# RHD2132_lvds_headstage_50mil.net
KiCad netlist of a schematic drawn in EAGLE
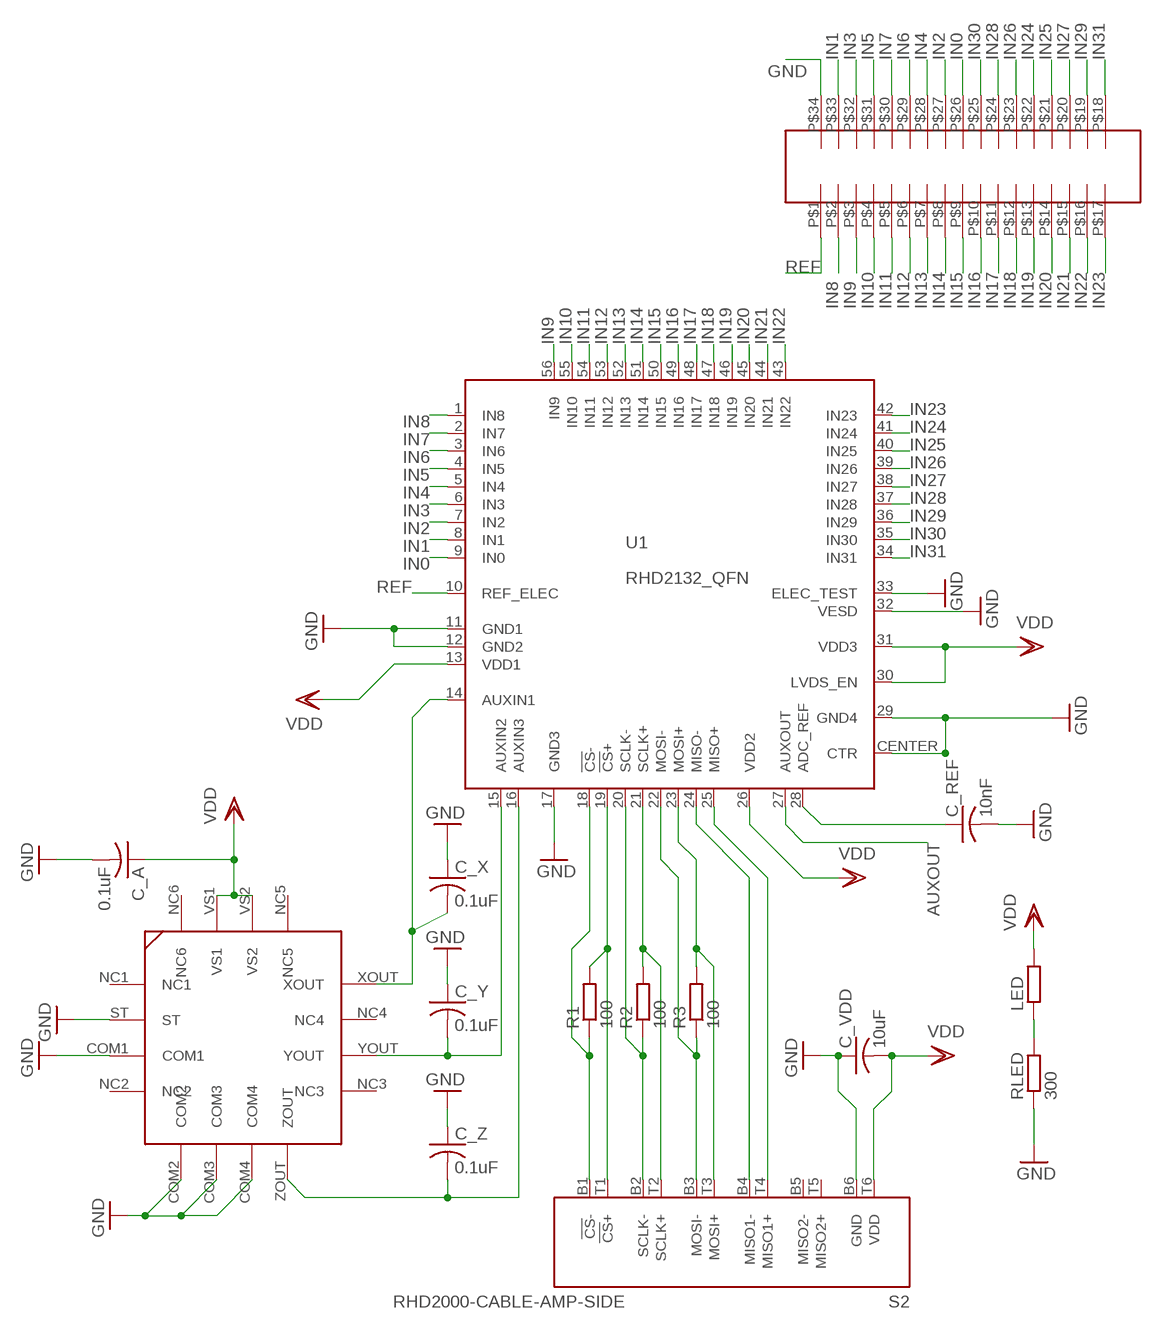
[diagram p0: schematic, sheet 1]

(export (version "E")
  (design (tool "Eeschema 10.0.6"))
  (components
    (comp (ref "C_A")
      (value "0.1uF")
      (footprint "eagle-import:C0402K")
      (libsource (lib "eagle-import") (part "C-USC0402K"))
    )
    (comp (ref "C_REF")
      (value "10nF")
      (footprint "eagle-import:C0402K")
      (libsource (lib "eagle-import") (part "C-USC0402K"))
    )
    (comp (ref "C_VDD")
      (value "10uF")
      (footprint "eagle-import:C0402K")
      (libsource (lib "eagle-import") (part "C-USC0402K"))
    )
    (comp (ref "C_X")
      (value "0.1uF")
      (footprint "eagle-import:C0402K")
      (libsource (lib "eagle-import") (part "C-USC0402K"))
    )
    (comp (ref "C_Y")
      (value "0.1uF")
      (footprint "eagle-import:C0402K")
      (libsource (lib "eagle-import") (part "C-USC0402K"))
    )
    (comp (ref "C_Z")
      (value "0.1uF")
      (footprint "eagle-import:C0402K")
      (libsource (lib "eagle-import") (part "C-USC0402K"))
    )
    (comp (ref "LED")
      (value "R-EU_R0402")
      (footprint "eagle-import:R0402")
      (libsource (lib "eagle-import") (part "R-EU_R0402"))
    )
    (comp (ref "R1")
      (value "100")
      (footprint "eagle-import:R0402")
      (libsource (lib "eagle-import") (part "R-EU_R0402"))
    )
    (comp (ref "R2")
      (value "100")
      (footprint "eagle-import:R0402")
      (libsource (lib "eagle-import") (part "R-EU_R0402"))
    )
    (comp (ref "R3")
      (value "100")
      (footprint "eagle-import:R0402")
      (libsource (lib "eagle-import") (part "R-EU_R0402"))
    )
    (comp (ref "RLED")
      (value "300")
      (footprint "eagle-import:R0402")
      (libsource (lib "eagle-import") (part "R-EU_R0402"))
    )
    (comp (ref "S2")
      (value "RHD2000-CABLE-AMP-SIDE")
      (footprint "eagle-import:OMNETICS_PZN-12-AA")
      (libsource (lib "eagle-import") (part "RHD2000-CABLE-AMP-SIDE"))
    )
    (comp (ref "U$1")
      (value "ADXL335")
      (footprint "eagle-import:ADXL335")
      (libsource (lib "eagle-import") (part "ADXL335"))
    )
    (comp (ref "U$2")
      (value "MILL-MAX17X2")
      (footprint "eagle-import:MILL-MAX17X2SMD")
      (libsource (lib "eagle-import") (part "MILL-MAX17X2"))
    )
    (comp (ref "U1")
      (value "RHD2132_QFN")
      (footprint "eagle-import:QFN56_8_X_8_LARGE")
      (libsource (lib "eagle-import") (part "RHD2132_QFN"))
    )
  )
  (nets
    (net (code "1") (name "/AUXOUT") (class "Default")
      (node (ref "U1") (pin "27") (pinfunction "AUXOUT_27") (pintype "tri_state"))
    )
    (net (code "2") (name "/IN0") (class "Default")
      (node (ref "U$2") (pin "P$26") (pinfunction "P$26_P$26") (pintype "bidirectional"))
      (node (ref "U1") (pin "9") (pinfunction "IN0_9") (pintype "input"))
    )
    (net (code "3") (name "/IN1") (class "Default")
      (node (ref "U$2") (pin "P$33") (pinfunction "P$33_P$33") (pintype "bidirectional"))
      (node (ref "U1") (pin "8") (pinfunction "IN1_8") (pintype "input"))
    )
    (net (code "4") (name "/IN2") (class "Default")
      (node (ref "U$2") (pin "P$27") (pinfunction "P$27_P$27") (pintype "bidirectional"))
      (node (ref "U1") (pin "7") (pinfunction "IN2_7") (pintype "input"))
    )
    (net (code "5") (name "/IN3") (class "Default")
      (node (ref "U$2") (pin "P$32") (pinfunction "P$32_P$32") (pintype "bidirectional"))
      (node (ref "U1") (pin "6") (pinfunction "IN3_6") (pintype "input"))
    )
    (net (code "6") (name "/IN4") (class "Default")
      (node (ref "U$2") (pin "P$28") (pinfunction "P$28_P$28") (pintype "bidirectional"))
      (node (ref "U1") (pin "5") (pinfunction "IN4_5") (pintype "input"))
    )
    (net (code "7") (name "/IN5") (class "Default")
      (node (ref "U$2") (pin "P$31") (pinfunction "P$31_P$31") (pintype "bidirectional"))
      (node (ref "U1") (pin "4") (pinfunction "IN5_4") (pintype "input"))
    )
    (net (code "8") (name "/IN6") (class "Default")
      (node (ref "U$2") (pin "P$29") (pinfunction "P$29_P$29") (pintype "bidirectional"))
      (node (ref "U1") (pin "3") (pinfunction "IN6_3") (pintype "input"))
    )
    (net (code "9") (name "/IN7") (class "Default")
      (node (ref "U$2") (pin "P$30") (pinfunction "P$30_P$30") (pintype "bidirectional"))
      (node (ref "U1") (pin "2") (pinfunction "IN7_2") (pintype "input"))
    )
    (net (code "10") (name "/IN8") (class "Default")
      (node (ref "U$2") (pin "P$2") (pinfunction "P$2_P$2") (pintype "bidirectional"))
      (node (ref "U1") (pin "1") (pinfunction "IN8_1") (pintype "input"))
    )
    (net (code "11") (name "/IN9") (class "Default")
      (node (ref "U$2") (pin "P$3") (pinfunction "P$3_P$3") (pintype "bidirectional"))
      (node (ref "U1") (pin "56") (pinfunction "IN9_56") (pintype "input"))
    )
    (net (code "12") (name "/IN10") (class "Default")
      (node (ref "U$2") (pin "P$4") (pinfunction "P$4_P$4") (pintype "bidirectional"))
      (node (ref "U1") (pin "55") (pinfunction "IN10_55") (pintype "input"))
    )
    (net (code "13") (name "/IN11") (class "Default")
      (node (ref "U$2") (pin "P$5") (pinfunction "P$5_P$5") (pintype "bidirectional"))
      (node (ref "U1") (pin "54") (pinfunction "IN11_54") (pintype "input"))
    )
    (net (code "14") (name "/IN12") (class "Default")
      (node (ref "U$2") (pin "P$6") (pinfunction "P$6_P$6") (pintype "bidirectional"))
      (node (ref "U1") (pin "53") (pinfunction "IN12_53") (pintype "input"))
    )
    (net (code "15") (name "/IN13") (class "Default")
      (node (ref "U$2") (pin "P$7") (pinfunction "P$7_P$7") (pintype "bidirectional"))
      (node (ref "U1") (pin "52") (pinfunction "IN13_52") (pintype "input"))
    )
    (net (code "16") (name "/IN14") (class "Default")
      (node (ref "U$2") (pin "P$8") (pinfunction "P$8_P$8") (pintype "bidirectional"))
      (node (ref "U1") (pin "51") (pinfunction "IN14_51") (pintype "input"))
    )
    (net (code "17") (name "/IN15") (class "Default")
      (node (ref "U$2") (pin "P$9") (pinfunction "P$9_P$9") (pintype "bidirectional"))
      (node (ref "U1") (pin "50") (pinfunction "IN15_50") (pintype "input"))
    )
    (net (code "18") (name "/IN16") (class "Default")
      (node (ref "U$2") (pin "P$10") (pinfunction "P$10_P$10") (pintype "bidirectional"))
      (node (ref "U1") (pin "49") (pinfunction "IN16_49") (pintype "input"))
    )
    (net (code "19") (name "/IN17") (class "Default")
      (node (ref "U$2") (pin "P$11") (pinfunction "P$11_P$11") (pintype "bidirectional"))
      (node (ref "U1") (pin "48") (pinfunction "IN17_48") (pintype "input"))
    )
    (net (code "20") (name "/IN18") (class "Default")
      (node (ref "U$2") (pin "P$12") (pinfunction "P$12_P$12") (pintype "bidirectional"))
      (node (ref "U1") (pin "47") (pinfunction "IN18_47") (pintype "input"))
    )
    (net (code "21") (name "/IN19") (class "Default")
      (node (ref "U$2") (pin "P$13") (pinfunction "P$13_P$13") (pintype "bidirectional"))
      (node (ref "U1") (pin "46") (pinfunction "IN19_46") (pintype "input"))
    )
    (net (code "22") (name "/IN20") (class "Default")
      (node (ref "U$2") (pin "P$14") (pinfunction "P$14_P$14") (pintype "bidirectional"))
      (node (ref "U1") (pin "45") (pinfunction "IN20_45") (pintype "input"))
    )
    (net (code "23") (name "/IN21") (class "Default")
      (node (ref "U$2") (pin "P$15") (pinfunction "P$15_P$15") (pintype "bidirectional"))
      (node (ref "U1") (pin "44") (pinfunction "IN21_44") (pintype "input"))
    )
    (net (code "24") (name "/IN22") (class "Default")
      (node (ref "U$2") (pin "P$16") (pinfunction "P$16_P$16") (pintype "bidirectional"))
      (node (ref "U1") (pin "43") (pinfunction "IN22_43") (pintype "input"))
    )
    (net (code "25") (name "/IN23") (class "Default")
      (node (ref "U$2") (pin "P$17") (pinfunction "P$17_P$17") (pintype "bidirectional"))
      (node (ref "U1") (pin "42") (pinfunction "IN23_42") (pintype "input"))
    )
    (net (code "26") (name "/IN24") (class "Default")
      (node (ref "U$2") (pin "P$22") (pinfunction "P$22_P$22") (pintype "bidirectional"))
      (node (ref "U1") (pin "41") (pinfunction "IN24_41") (pintype "input"))
    )
    (net (code "27") (name "/IN25") (class "Default")
      (node (ref "U$2") (pin "P$21") (pinfunction "P$21_P$21") (pintype "bidirectional"))
      (node (ref "U1") (pin "40") (pinfunction "IN25_40") (pintype "input"))
    )
    (net (code "28") (name "/IN26") (class "Default")
      (node (ref "U$2") (pin "P$23") (pinfunction "P$23_P$23") (pintype "bidirectional"))
      (node (ref "U1") (pin "39") (pinfunction "IN26_39") (pintype "input"))
    )
    (net (code "29") (name "/IN27") (class "Default")
      (node (ref "U$2") (pin "P$20") (pinfunction "P$20_P$20") (pintype "bidirectional"))
      (node (ref "U1") (pin "38") (pinfunction "IN27_38") (pintype "input"))
    )
    (net (code "30") (name "/IN28") (class "Default")
      (node (ref "U$2") (pin "P$24") (pinfunction "P$24_P$24") (pintype "bidirectional"))
      (node (ref "U1") (pin "37") (pinfunction "IN28_37") (pintype "input"))
    )
    (net (code "31") (name "/IN29") (class "Default")
      (node (ref "U$2") (pin "P$19") (pinfunction "P$19_P$19") (pintype "bidirectional"))
      (node (ref "U1") (pin "36") (pinfunction "IN29_36") (pintype "input"))
    )
    (net (code "32") (name "/IN30") (class "Default")
      (node (ref "U$2") (pin "P$25") (pinfunction "P$25_P$25") (pintype "bidirectional"))
      (node (ref "U1") (pin "35") (pinfunction "IN30_35") (pintype "input"))
    )
    (net (code "33") (name "/IN31") (class "Default")
      (node (ref "U$2") (pin "P$18") (pinfunction "P$18_P$18") (pintype "bidirectional"))
      (node (ref "U1") (pin "34") (pinfunction "IN31_34") (pintype "input"))
    )
    (net (code "34") (name "/REF") (class "Default")
      (node (ref "U$2") (pin "P$1") (pinfunction "P$1_P$1") (pintype "bidirectional"))
      (node (ref "U1") (pin "10") (pinfunction "REF_ELEC_10") (pintype "input"))
    )
    (net (code "35") (name "GND") (class "Default")
      (node (ref "C_A") (pin "2") (pinfunction "2_2") (pintype "passive"))
      (node (ref "C_REF") (pin "2") (pinfunction "2_2") (pintype "passive"))
      (node (ref "C_VDD") (pin "1") (pinfunction "1_1") (pintype "passive"))
      (node (ref "C_X") (pin "1") (pinfunction "1_1") (pintype "passive"))
      (node (ref "C_Y") (pin "1") (pinfunction "1_1") (pintype "passive"))
      (node (ref "C_Z") (pin "1") (pinfunction "1_1") (pintype "passive"))
      (node (ref "RLED") (pin "1") (pinfunction "1_1") (pintype "passive"))
      (node (ref "S2") (pin "B6") (pinfunction "GND_B6") (pintype "power_in"))
      (node (ref "U$1") (pin "COM1") (pinfunction "COM1_COM1") (pintype "bidirectional"))
      (node (ref "U$1") (pin "COM2") (pinfunction "COM2_COM2") (pintype "bidirectional"))
      (node (ref "U$1") (pin "COM3") (pinfunction "COM3_COM3") (pintype "bidirectional"))
      (node (ref "U$1") (pin "COM4") (pinfunction "COM4_COM4") (pintype "bidirectional"))
      (node (ref "U$1") (pin "ST") (pinfunction "ST_ST") (pintype "bidirectional"))
      (node (ref "U$2") (pin "P$34") (pinfunction "P$34_P$34") (pintype "bidirectional"))
      (node (ref "U1") (pin "11") (pinfunction "GND1_11") (pintype "power_in"))
      (node (ref "U1") (pin "12") (pinfunction "GND2_12") (pintype "power_in"))
      (node (ref "U1") (pin "17") (pinfunction "GND3_17") (pintype "power_in"))
      (node (ref "U1") (pin "29") (pinfunction "GND4_29") (pintype "power_in"))
      (node (ref "U1") (pin "32") (pinfunction "VESD_32") (pintype "power_in"))
      (node (ref "U1") (pin "33") (pinfunction "ELEC_TEST_33") (pintype "input"))
      (node (ref "U1") (pin "CENTER") (pinfunction "CTR_CENTER") (pintype "power_in"))
    )
    (net (code "36") (name "Net-(LED-Pad1)") (class "Default")
      (node (ref "LED") (pin "1") (pinfunction "1_1") (pintype "passive"))
      (node (ref "RLED") (pin "2") (pinfunction "2_2") (pintype "passive"))
    )
    (net (code "37") (name "Net-(S2-MISO1+)") (class "Default")
      (node (ref "S2") (pin "T4") (pinfunction "MISO1+_T4") (pintype "bidirectional"))
      (node (ref "U1") (pin "25") (pinfunction "MISO+_25") (pintype "output"))
    )
    (net (code "38") (name "Net-(S2-MISO1-)") (class "Default")
      (node (ref "S2") (pin "B4") (pinfunction "MISO1-_B4") (pintype "bidirectional"))
      (node (ref "U1") (pin "24") (pinfunction "MISO-_24") (pintype "output"))
    )
    (net (code "39") (name "Net-(S2-MOSI+)") (class "Default")
      (node (ref "R3") (pin "2") (pinfunction "2_2") (pintype "passive"))
      (node (ref "S2") (pin "T3") (pinfunction "MOSI+_T3") (pintype "bidirectional"))
      (node (ref "U1") (pin "23") (pinfunction "MOSI+_23") (pintype "input"))
    )
    (net (code "40") (name "Net-(S2-MOSI-)") (class "Default")
      (node (ref "R3") (pin "1") (pinfunction "1_1") (pintype "passive"))
      (node (ref "S2") (pin "B3") (pinfunction "MOSI-_B3") (pintype "bidirectional"))
      (node (ref "U1") (pin "22") (pinfunction "MOSI-_22") (pintype "input"))
    )
    (net (code "41") (name "Net-(S2-SCLK+)") (class "Default")
      (node (ref "R2") (pin "2") (pinfunction "2_2") (pintype "passive"))
      (node (ref "S2") (pin "T2") (pinfunction "SCLK+_T2") (pintype "bidirectional"))
      (node (ref "U1") (pin "21") (pinfunction "SCLK+_21") (pintype "input"))
    )
    (net (code "42") (name "Net-(S2-SCLK-)") (class "Default")
      (node (ref "R2") (pin "1") (pinfunction "1_1") (pintype "passive"))
      (node (ref "S2") (pin "B2") (pinfunction "SCLK-_B2") (pintype "bidirectional"))
      (node (ref "U1") (pin "20") (pinfunction "SCLK-_20") (pintype "input"))
    )
    (net (code "43") (name "Net-(S2-~{CS}+)") (class "Default")
      (node (ref "R1") (pin "2") (pinfunction "2_2") (pintype "passive"))
      (node (ref "S2") (pin "T1") (pinfunction "~{CS}+_T1") (pintype "bidirectional"))
      (node (ref "U1") (pin "19") (pinfunction "~{CS}+_19") (pintype "input"))
    )
    (net (code "44") (name "Net-(S2-~{CS}-)") (class "Default")
      (node (ref "R1") (pin "1") (pinfunction "1_1") (pintype "passive"))
      (node (ref "S2") (pin "B1") (pinfunction "~{CS}-_B1") (pintype "bidirectional"))
      (node (ref "U1") (pin "18") (pinfunction "~{CS}-_18") (pintype "input"))
    )
    (net (code "45") (name "Net-(U1-ADC_REF)") (class "Default")
      (node (ref "C_REF") (pin "1") (pinfunction "1_1") (pintype "passive"))
      (node (ref "U1") (pin "28") (pinfunction "ADC_REF_28") (pintype "passive"))
    )
    (net (code "46") (name "Net-(U1-AUXIN1)") (class "Default")
      (node (ref "C_X") (pin "2") (pinfunction "2_2") (pintype "passive"))
      (node (ref "U$1") (pin "XOUT") (pinfunction "XOUT_XOUT") (pintype "bidirectional"))
      (node (ref "U1") (pin "14") (pinfunction "AUXIN1_14") (pintype "input"))
    )
    (net (code "47") (name "Net-(U1-AUXIN2)") (class "Default")
      (node (ref "C_Y") (pin "2") (pinfunction "2_2") (pintype "passive"))
      (node (ref "U$1") (pin "YOUT") (pinfunction "YOUT_YOUT") (pintype "bidirectional"))
      (node (ref "U1") (pin "15") (pinfunction "AUXIN2_15") (pintype "input"))
    )
    (net (code "48") (name "Net-(U1-AUXIN3)") (class "Default")
      (node (ref "C_Z") (pin "2") (pinfunction "2_2") (pintype "passive"))
      (node (ref "U$1") (pin "ZOUT") (pinfunction "ZOUT_ZOUT") (pintype "bidirectional"))
      (node (ref "U1") (pin "16") (pinfunction "AUXIN3_16") (pintype "input"))
    )
    (net (code "49") (name "VDD") (class "Default")
      (node (ref "C_A") (pin "1") (pinfunction "1_1") (pintype "passive"))
      (node (ref "C_VDD") (pin "2") (pinfunction "2_2") (pintype "passive"))
      (node (ref "LED") (pin "2") (pinfunction "2_2") (pintype "passive"))
      (node (ref "S2") (pin "T6") (pinfunction "VDD_T6") (pintype "bidirectional"))
      (node (ref "U$1") (pin "VS1") (pinfunction "VS1_VS1") (pintype "bidirectional"))
      (node (ref "U$1") (pin "VS2") (pinfunction "VS2_VS2") (pintype "bidirectional"))
      (node (ref "U1") (pin "13") (pinfunction "VDD1_13") (pintype "power_in"))
      (node (ref "U1") (pin "26") (pinfunction "VDD2_26") (pintype "power_in"))
      (node (ref "U1") (pin "30") (pinfunction "LVDS_EN_30") (pintype "input"))
      (node (ref "U1") (pin "31") (pinfunction "VDD3_31") (pintype "power_in"))
    )
    (net (code "50") (name "unconnected-(S2-MISO2+-PadT5)") (class "Default")
      (node (ref "S2") (pin "T5") (pinfunction "MISO2+_T5") (pintype "bidirectional"))
    )
    (net (code "51") (name "unconnected-(S2-MISO2--PadB5)") (class "Default")
      (node (ref "S2") (pin "B5") (pinfunction "MISO2-_B5") (pintype "bidirectional"))
    )
    (net (code "52") (name "unconnected-(U$1-PadNC1)") (class "Default")
      (node (ref "U$1") (pin "NC1") (pinfunction "NC1_NC1") (pintype "bidirectional"))
    )
    (net (code "53") (name "unconnected-(U$1-PadNC2)") (class "Default")
      (node (ref "U$1") (pin "NC2") (pinfunction "NC2_NC2") (pintype "bidirectional"))
    )
    (net (code "54") (name "unconnected-(U$1-PadNC3)") (class "Default")
      (node (ref "U$1") (pin "NC3") (pinfunction "NC3_NC3") (pintype "bidirectional"))
    )
    (net (code "55") (name "unconnected-(U$1-PadNC4)") (class "Default")
      (node (ref "U$1") (pin "NC4") (pinfunction "NC4_NC4") (pintype "bidirectional"))
    )
    (net (code "56") (name "unconnected-(U$1-PadNC5)") (class "Default")
      (node (ref "U$1") (pin "NC5") (pinfunction "NC5_NC5") (pintype "bidirectional"))
    )
    (net (code "57") (name "unconnected-(U$1-PadNC6)") (class "Default")
      (node (ref "U$1") (pin "NC6") (pinfunction "NC6_NC6") (pintype "bidirectional"))
    )
  )
)
